# NAKUJA_REMIX.net
KiCad netlist of a schematic drawn in EasyEDA
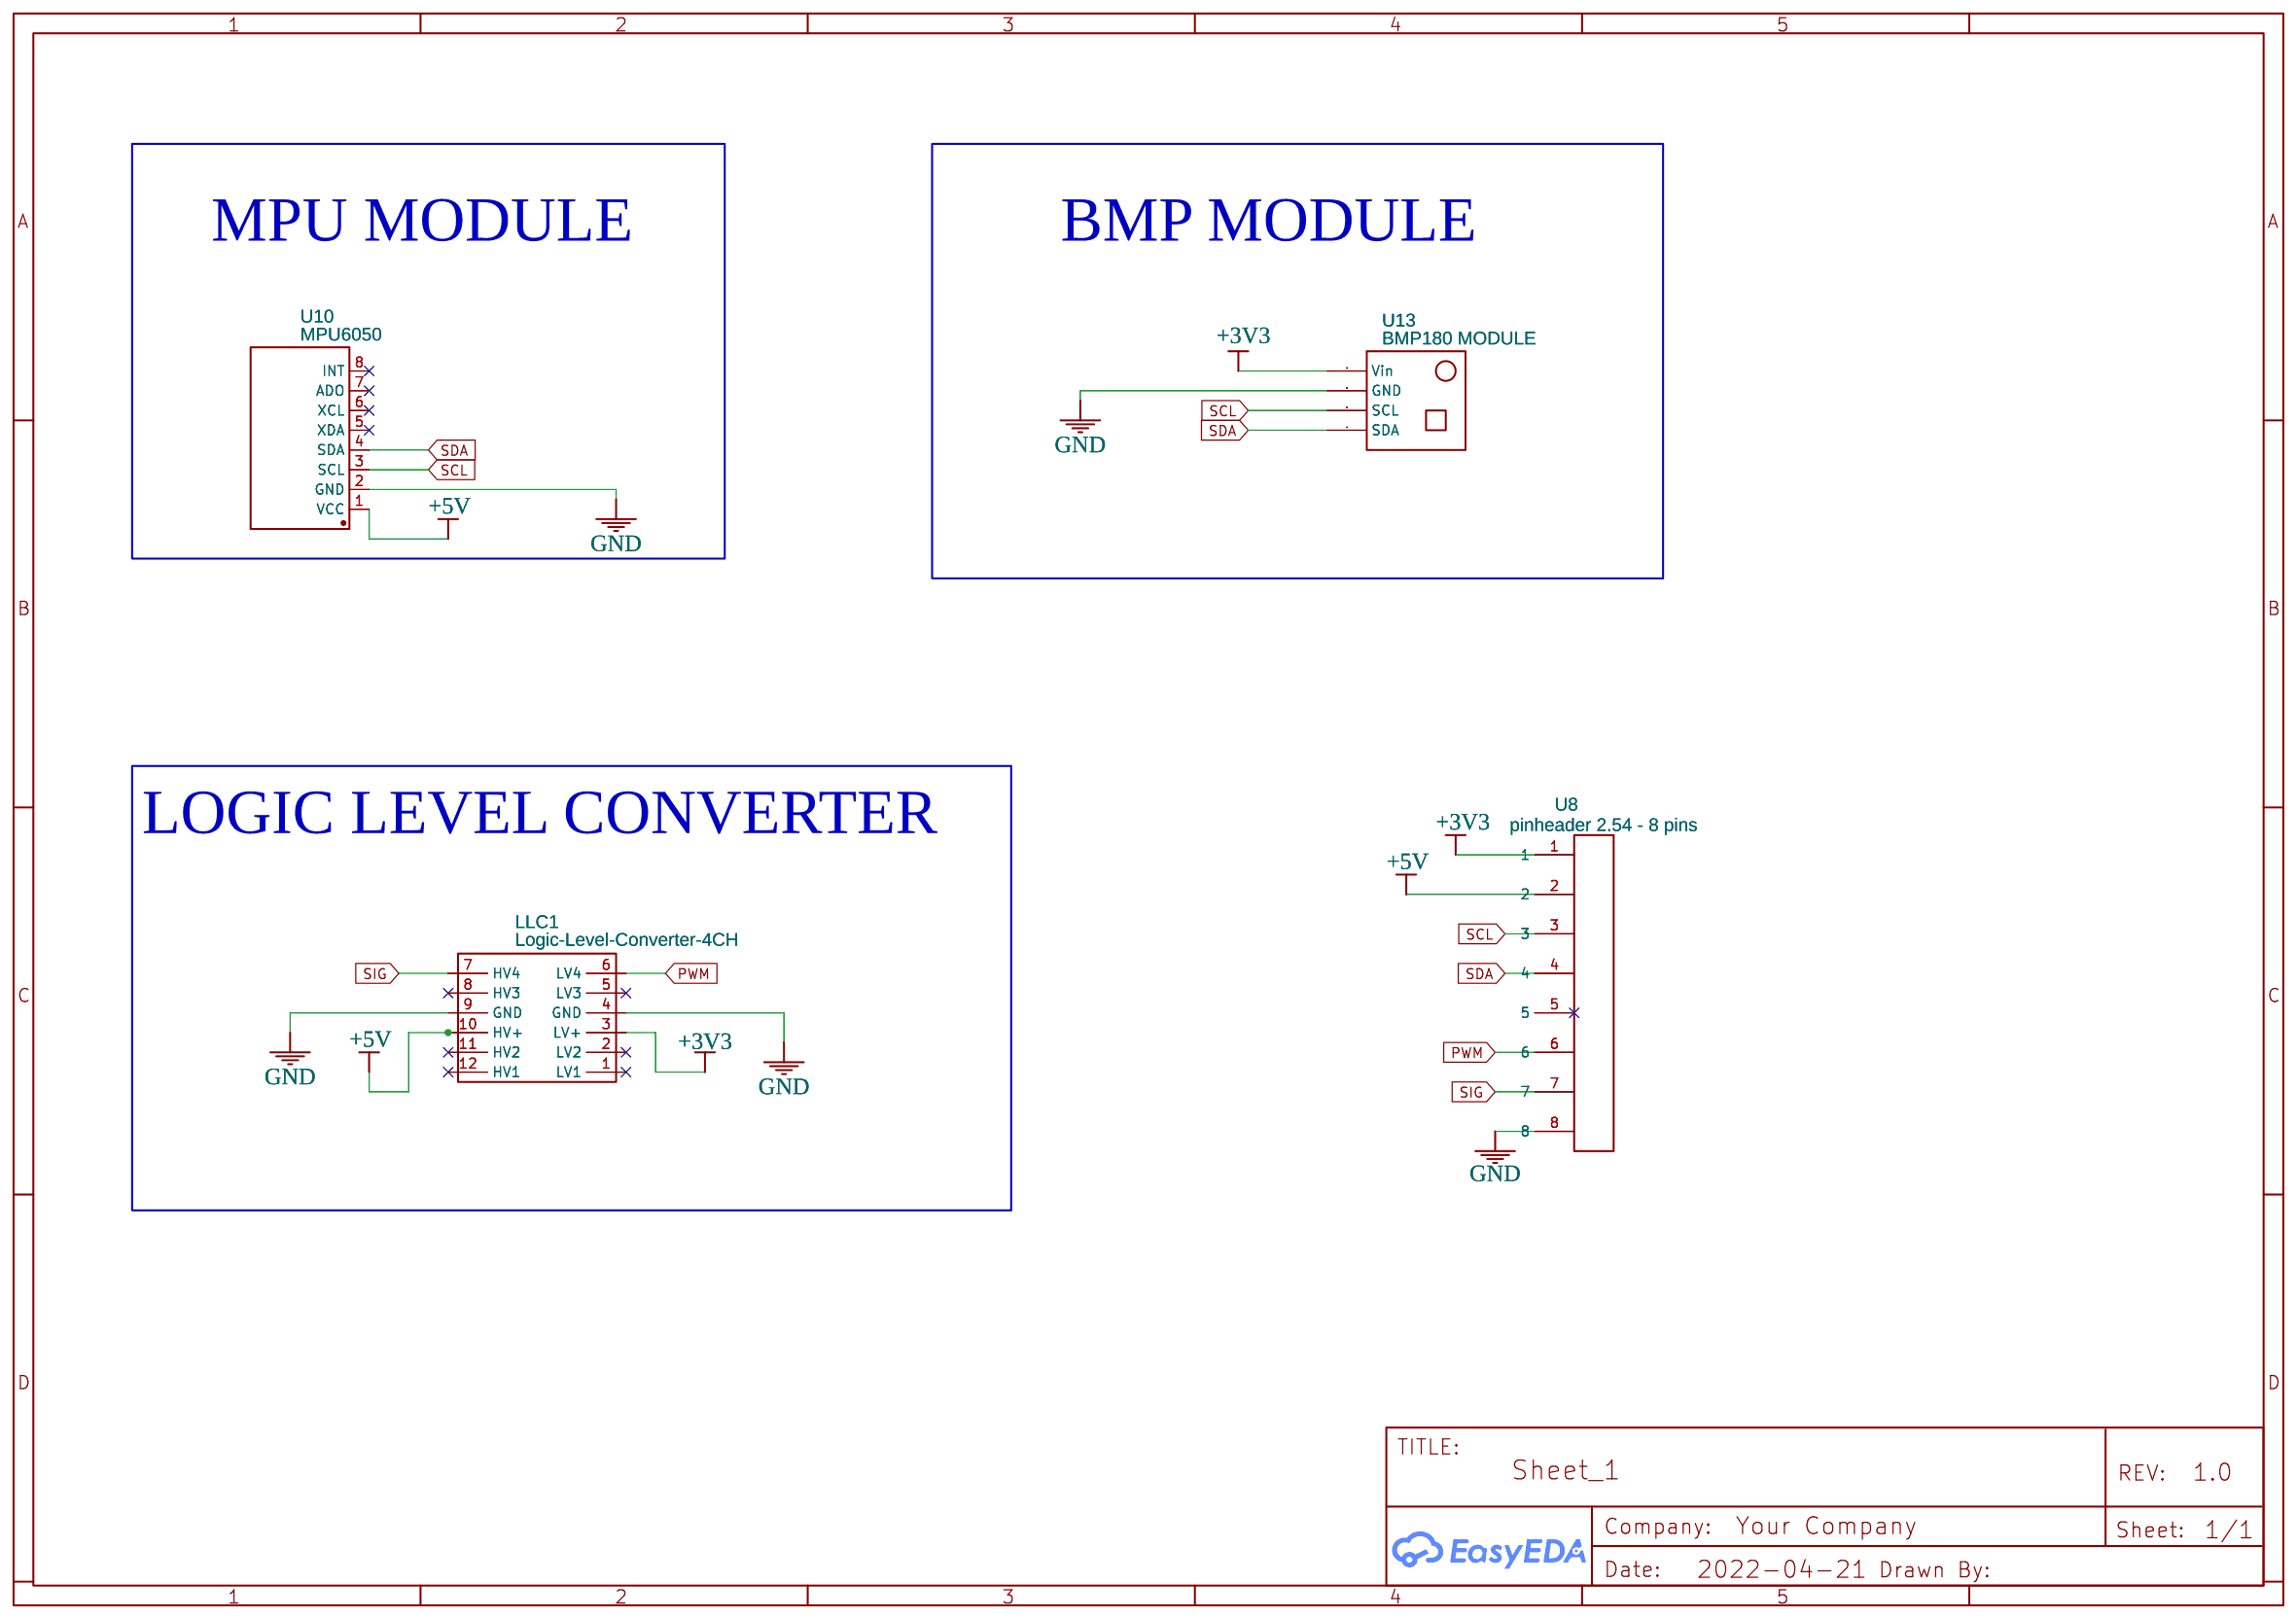
[diagram p0: schematic sheet]

(export (version "E")
  (design (tool "Eeschema 10.0.6"))
  (components
    (comp (ref "LLC1")
      (value "Logic-Level-Converter-4CH")
      (fields (field (name "BOM_Supplier Part") "50807"))
      (libsource (lib "") (part "Logic-Level-Converter-4CH"))
    )
    (comp (ref "U8") (value "pinheader 2.54 - 8 pins") (libsource (lib "") (part "pinheader 2.54 - 8 pins")))
    (comp (ref "U10")
      (value "MPU6050")
      (fields (field (name "BOM_Supplier Part") "GY521"))
      (libsource (lib "") (part "MPU6050"))
    )
    (comp (ref "U13")
      (value "BMP180 MODULE")
      (fields (field (name "BOM_Manufacturer Part") "BMP180 (HW-596)"))
      (libsource (lib "") (part "BMP180 MODULE"))
    )
  )
  (nets
    (net (code "1") (name "+3V3") (class "Default")
      (node (ref "LLC1") (pin "3") (pinfunction "LV+_3") (pintype "unspecified"))
      (node (ref "U13") (pin "1") (pinfunction "Vin_1") (pintype "unspecified"))
      (node (ref "U8") (pin "1") (pinfunction "1_1") (pintype "unspecified"))
    )
    (net (code "2") (name "+5V") (class "Default")
      (node (ref "LLC1") (pin "10") (pinfunction "HV+_10") (pintype "unspecified"))
      (node (ref "U10") (pin "1") (pinfunction "VCC_1") (pintype "unspecified"))
      (node (ref "U8") (pin "2") (pinfunction "2_2") (pintype "unspecified"))
    )
    (net (code "3") (name "GND") (class "Default")
      (node (ref "LLC1") (pin "4") (pinfunction "GND_4") (pintype "unspecified"))
      (node (ref "LLC1") (pin "9") (pinfunction "GND_9") (pintype "unspecified"))
      (node (ref "U10") (pin "2") (pinfunction "GND_2") (pintype "unspecified"))
      (node (ref "U13") (pin "2") (pinfunction "GND_2") (pintype "unspecified"))
      (node (ref "U8") (pin "8") (pinfunction "8_8") (pintype "unspecified"))
    )
    (net (code "4") (name "PWM") (class "Default")
      (node (ref "LLC1") (pin "6") (pinfunction "LV4_6") (pintype "unspecified"))
      (node (ref "U8") (pin "6") (pinfunction "6_6") (pintype "unspecified"))
    )
    (net (code "5") (name "SCL") (class "Default")
      (node (ref "U10") (pin "3") (pinfunction "SCL_3") (pintype "unspecified"))
      (node (ref "U13") (pin "3") (pinfunction "SCL_3") (pintype "unspecified"))
      (node (ref "U8") (pin "3") (pinfunction "3_3") (pintype "unspecified"))
    )
    (net (code "6") (name "SDA") (class "Default")
      (node (ref "U10") (pin "4") (pinfunction "SDA_4") (pintype "unspecified"))
      (node (ref "U13") (pin "4") (pinfunction "SDA_4") (pintype "unspecified"))
      (node (ref "U8") (pin "4") (pinfunction "4_4") (pintype "unspecified"))
    )
    (net (code "7") (name "SIG") (class "Default")
      (node (ref "LLC1") (pin "7") (pinfunction "HV4_7") (pintype "unspecified"))
      (node (ref "U8") (pin "7") (pinfunction "7_7") (pintype "unspecified"))
    )
    (net (code "8") (name "unconnected-(LLC1-HV1-Pad12)") (class "Default")
      (node (ref "LLC1") (pin "12") (pinfunction "HV1_12") (pintype "unspecified+no_connect"))
    )
    (net (code "9") (name "unconnected-(LLC1-HV2-Pad11)") (class "Default")
      (node (ref "LLC1") (pin "11") (pinfunction "HV2_11") (pintype "unspecified+no_connect"))
    )
    (net (code "10") (name "unconnected-(LLC1-HV3-Pad8)") (class "Default")
      (node (ref "LLC1") (pin "8") (pinfunction "HV3_8") (pintype "unspecified+no_connect"))
    )
    (net (code "11") (name "unconnected-(LLC1-LV1-Pad1)") (class "Default")
      (node (ref "LLC1") (pin "1") (pinfunction "LV1_1") (pintype "unspecified+no_connect"))
    )
    (net (code "12") (name "unconnected-(LLC1-LV2-Pad2)") (class "Default")
      (node (ref "LLC1") (pin "2") (pinfunction "LV2_2") (pintype "unspecified+no_connect"))
    )
    (net (code "13") (name "unconnected-(LLC1-LV3-Pad5)") (class "Default")
      (node (ref "LLC1") (pin "5") (pinfunction "LV3_5") (pintype "unspecified+no_connect"))
    )
    (net (code "14") (name "unconnected-(U8-Pad5)") (class "Default")
      (node (ref "U8") (pin "5") (pinfunction "5_5") (pintype "unspecified+no_connect"))
    )
    (net (code "15") (name "unconnected-(U10-ADO-Pad7)") (class "Default")
      (node (ref "U10") (pin "7") (pinfunction "ADO_7") (pintype "unspecified+no_connect"))
    )
    (net (code "16") (name "unconnected-(U10-INT-Pad8)") (class "Default")
      (node (ref "U10") (pin "8") (pinfunction "INT_8") (pintype "unspecified+no_connect"))
    )
    (net (code "17") (name "unconnected-(U10-XCL-Pad6)") (class "Default")
      (node (ref "U10") (pin "6") (pinfunction "XCL_6") (pintype "unspecified+no_connect"))
    )
    (net (code "18") (name "unconnected-(U10-XDA-Pad5)") (class "Default")
      (node (ref "U10") (pin "5") (pinfunction "XDA_5") (pintype "unspecified+no_connect"))
    )
  )
)
